# skin_orch.net
KiCad netlist of a schematic drawn in EAGLE
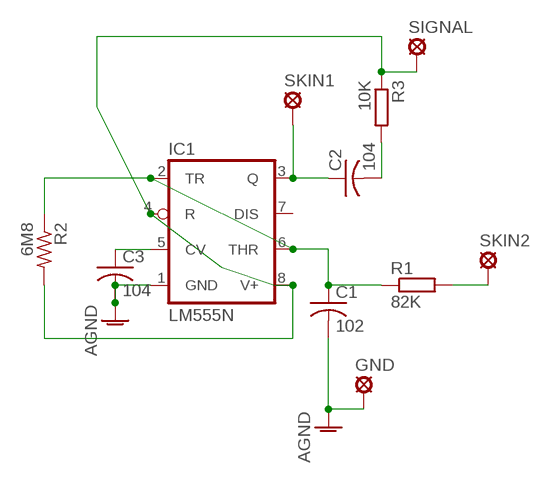
[diagram p0: schematic, sheet 1]

(export (version "E")
  (design (tool "Eeschema 10.0.6"))
  (components
    (comp (ref "C1")
      (value "102")
      (footprint "eagle-import:C025-030X050")
      (libsource (lib "eagle-import") (part "C-US025-030X050"))
    )
    (comp (ref "C2")
      (value "104")
      (footprint "eagle-import:C025-030X050")
      (libsource (lib "eagle-import") (part "C-US025-030X050"))
    )
    (comp (ref "C3")
      (value "104")
      (footprint "eagle-import:C025-030X050")
      (libsource (lib "eagle-import") (part "C-US025-030X050"))
    )
    (comp (ref "GND")
      (value "LSP10")
      (footprint "eagle-import:LSP10")
      (libsource (lib "eagle-import") (part "LSP10"))
    )
    (comp (ref "IC1")
      (value "LM555N")
      (footprint "eagle-import:DIL08")
      (libsource (lib "eagle-import") (part "555NLM"))
    )
    (comp (ref "R1")
      (value "82K")
      (footprint "eagle-import:0207_2V")
      (libsource (lib "eagle-import") (part "R-EU_0207/2V"))
    )
    (comp (ref "R2")
      (value "6M8")
      (footprint "eagle-import:0207_7")
      (libsource (lib "eagle-import") (part "R-US_0207/7"))
    )
    (comp (ref "R3")
      (value "10K")
      (footprint "eagle-import:0207_2V")
      (libsource (lib "eagle-import") (part "R-EU_0207/2V"))
    )
    (comp (ref "SIGNAL")
      (value "LSP10")
      (footprint "eagle-import:LSP10")
      (libsource (lib "eagle-import") (part "LSP10"))
    )
    (comp (ref "SKIN1")
      (value "LSP10")
      (footprint "eagle-import:LSP10")
      (libsource (lib "eagle-import") (part "LSP10"))
    )
    (comp (ref "SKIN2")
      (value "LSP10")
      (footprint "eagle-import:LSP10")
      (libsource (lib "eagle-import") (part "LSP10"))
    )
  )
  (nets
    (net (code "1") (name "AGND") (class "Default")
      (node (ref "C1") (pin "2") (pinfunction "2_2") (pintype "passive"))
      (node (ref "C3") (pin "2") (pinfunction "2_2") (pintype "passive"))
      (node (ref "GND") (pin "MP") (pinfunction "MP_MP") (pintype "passive"))
      (node (ref "IC1") (pin "1") (pinfunction "GND_1") (pintype "power_in"))
    )
    (net (code "2") (name "Net-(C2-Pad2)") (class "Default")
      (node (ref "C2") (pin "2") (pinfunction "2_2") (pintype "passive"))
      (node (ref "R3") (pin "2") (pinfunction "2_2") (pintype "passive"))
    )
    (net (code "3") (name "Net-(IC1-CV)") (class "Default")
      (node (ref "C3") (pin "1") (pinfunction "1_1") (pintype "passive"))
      (node (ref "IC1") (pin "5") (pinfunction "CV_5") (pintype "input"))
    )
    (net (code "4") (name "Net-(IC1-Q)") (class "Default")
      (node (ref "C2") (pin "1") (pinfunction "1_1") (pintype "passive"))
      (node (ref "IC1") (pin "3") (pinfunction "Q_3") (pintype "output"))
      (node (ref "SKIN1") (pin "MP") (pinfunction "MP_MP") (pintype "passive"))
    )
    (net (code "5") (name "Net-(IC1-R)") (class "Default")
      (node (ref "IC1") (pin "4") (pinfunction "R_4") (pintype "input"))
      (node (ref "IC1") (pin "8") (pinfunction "V+_8") (pintype "power_in"))
      (node (ref "R2") (pin "2") (pinfunction "2_2") (pintype "passive"))
      (node (ref "R3") (pin "1") (pinfunction "1_1") (pintype "passive"))
      (node (ref "SIGNAL") (pin "MP") (pinfunction "MP_MP") (pintype "passive"))
    )
    (net (code "6") (name "Net-(IC1-THR)") (class "Default")
      (node (ref "C1") (pin "1") (pinfunction "1_1") (pintype "passive"))
      (node (ref "IC1") (pin "2") (pinfunction "TR_2") (pintype "input"))
      (node (ref "IC1") (pin "6") (pinfunction "THR_6") (pintype "input"))
      (node (ref "R1") (pin "1") (pinfunction "1_1") (pintype "passive"))
      (node (ref "R2") (pin "1") (pinfunction "1_1") (pintype "passive"))
    )
    (net (code "7") (name "Net-(R1-Pad2)") (class "Default")
      (node (ref "R1") (pin "2") (pinfunction "2_2") (pintype "passive"))
      (node (ref "SKIN2") (pin "MP") (pinfunction "MP_MP") (pintype "passive"))
    )
    (net (code "8") (name "unconnected-(IC1-DIS-Pad7)") (class "Default")
      (node (ref "IC1") (pin "7") (pinfunction "DIS_7") (pintype "input"))
    )
  )
)
